# ECE411-Group6.net
KiCad netlist of a schematic drawn in EAGLE
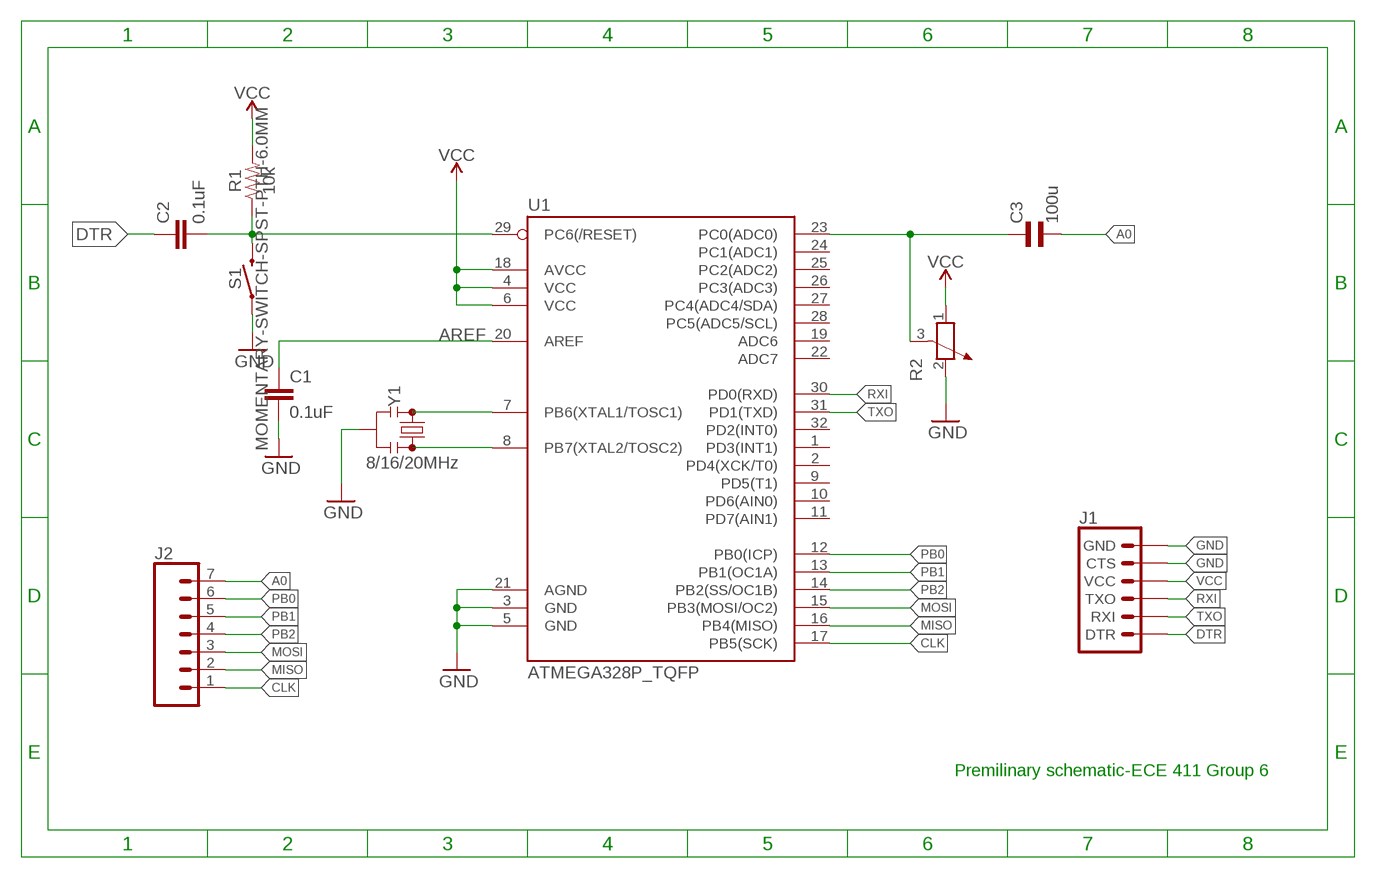
[diagram p0: schematic, sheet 1]

(export (version "E")
  (design (tool "Eeschema 10.0.6"))
  (components
    (comp (ref "C1")
      (value "0.1uF")
      (footprint "eagle-import:0603")
      (libsource (lib "eagle-import") (part "0.1UF-0603-25V-5%"))
    )
    (comp (ref "C2")
      (value "0.1uF")
      (footprint "eagle-import:0603")
      (libsource (lib "eagle-import") (part "0.1UF-0603-25V-5%"))
    )
    (comp (ref "C3")
      (value "100u")
      (footprint "eagle-import:EU25-10")
      (libsource (lib "eagle-import") (part "EL-BI25-10AXIAL"))
    )
    (comp (ref "J1")
      (value "6_PIN_SERIAL_TARGET")
      (footprint "eagle-import:1X06")
      (libsource (lib "eagle-import") (part "6_PIN_SERIAL_TARGET"))
    )
    (comp (ref "J2")
      (value "CONN_07")
      (footprint "eagle-import:1X07")
      (libsource (lib "eagle-import") (part "CONN_07"))
    )
    (comp (ref "R1")
      (value "10k")
      (footprint "eagle-import:0603")
      (libsource (lib "eagle-import") (part "10KOHM-0603-1/10W-1%"))
    )
    (comp (ref "R2")
      (value "POTENTIOMETER_PT-10")
      (footprint "eagle-import:PT-10")
      (libsource (lib "eagle-import") (part "POTENTIOMETER_PT-10"))
    )
    (comp (ref "S1")
      (value "MOMENTARY-SWITCH-SPST-PTH-6.0MM")
      (footprint "eagle-import:TACTILE_SWITCH_PTH_6.0MM")
      (libsource (lib "eagle-import") (part "MOMENTARY-SWITCH-SPST-PTH-6.0MM"))
    )
    (comp (ref "U1")
      (value "ATMEGA328P_TQFP")
      (footprint "eagle-import:TQFP32-08")
      (libsource (lib "eagle-import") (part "ATMEGA328P_TQFP"))
    )
    (comp (ref "Y1")
      (value "8/16/20MHz")
      (footprint "eagle-import:RESONATOR-SMD-3.2X1.3")
      (libsource (lib "eagle-import") (part "RESONATORSMD-3.2X1.3"))
    )
  )
  (nets
    (net (code "1") (name "/AREF") (class "Default")
      (node (ref "C1") (pin "1") (pinfunction "1_1") (pintype "passive"))
      (node (ref "U1") (pin "20") (pinfunction "AREF_20") (pintype "bidirectional"))
    )
    (net (code "2") (name "A0") (class "Default")
      (node (ref "C3") (pin "2") (pinfunction "2_2") (pintype "passive"))
      (node (ref "J2") (pin "7") (pinfunction "7_7") (pintype "passive"))
    )
    (net (code "3") (name "CLK") (class "Default")
      (node (ref "J2") (pin "1") (pinfunction "1_1") (pintype "passive"))
      (node (ref "U1") (pin "17") (pinfunction "PB5(SCK)_17") (pintype "bidirectional"))
    )
    (net (code "4") (name "DTR") (class "Default")
      (node (ref "C2") (pin "1") (pinfunction "1_1") (pintype "passive"))
      (node (ref "J1") (pin "1") (pinfunction "DTR_1") (pintype "passive"))
    )
    (net (code "5") (name "GND") (class "Default")
      (node (ref "C1") (pin "2") (pinfunction "2_2") (pintype "passive"))
      (node (ref "J1") (pin "5") (pinfunction "CTS_5") (pintype "passive"))
      (node (ref "J1") (pin "6") (pinfunction "GND_6") (pintype "passive"))
      (node (ref "R2") (pin "2") (pinfunction "2_2") (pintype "passive"))
      (node (ref "S1") (pin "1") (pinfunction "1_1") (pintype "passive"))
      (node (ref "U1") (pin "21") (pinfunction "AGND_21") (pintype "bidirectional"))
      (node (ref "U1") (pin "3") (pinfunction "GND_3") (pintype "bidirectional"))
      (node (ref "U1") (pin "5") (pinfunction "GND_5") (pintype "bidirectional"))
      (node (ref "Y1") (pin "2") (pinfunction "2_2") (pintype "passive"))
    )
    (net (code "6") (name "MISO") (class "Default")
      (node (ref "J2") (pin "2") (pinfunction "2_2") (pintype "passive"))
      (node (ref "U1") (pin "16") (pinfunction "PB4(MISO)_16") (pintype "bidirectional"))
    )
    (net (code "7") (name "MOSI") (class "Default")
      (node (ref "J2") (pin "3") (pinfunction "3_3") (pintype "passive"))
      (node (ref "U1") (pin "15") (pinfunction "PB3(MOSI/OC2)_15") (pintype "bidirectional"))
    )
    (net (code "8") (name "Net-(S1-2)") (class "Default")
      (node (ref "C2") (pin "2") (pinfunction "2_2") (pintype "passive"))
      (node (ref "R1") (pin "1") (pinfunction "1_1") (pintype "passive"))
      (node (ref "S1") (pin "3") (pinfunction "2_3") (pintype "passive"))
      (node (ref "U1") (pin "29") (pinfunction "PC6(/RESET)_29") (pintype "bidirectional"))
    )
    (net (code "9") (name "Net-(U1-PB6(XTAL1{slash}TOSC1))") (class "Default")
      (node (ref "U1") (pin "7") (pinfunction "PB6(XTAL1/TOSC1)_7") (pintype "bidirectional"))
      (node (ref "Y1") (pin "1") (pinfunction "1_1") (pintype "passive"))
    )
    (net (code "10") (name "Net-(U1-PB7(XTAL2{slash}TOSC2))") (class "Default")
      (node (ref "U1") (pin "8") (pinfunction "PB7(XTAL2/TOSC2)_8") (pintype "bidirectional"))
      (node (ref "Y1") (pin "3") (pinfunction "3_3") (pintype "passive"))
    )
    (net (code "11") (name "Net-(U1-PC0(ADC0))") (class "Default")
      (node (ref "C3") (pin "1") (pinfunction "1_1") (pintype "passive"))
      (node (ref "R2") (pin "3") (pinfunction "3_3") (pintype "passive"))
      (node (ref "U1") (pin "23") (pinfunction "PC0(ADC0)_23") (pintype "bidirectional"))
    )
    (net (code "12") (name "PB0") (class "Default")
      (node (ref "J2") (pin "6") (pinfunction "6_6") (pintype "passive"))
      (node (ref "U1") (pin "12") (pinfunction "PB0(ICP)_12") (pintype "bidirectional"))
    )
    (net (code "13") (name "PB1") (class "Default")
      (node (ref "J2") (pin "5") (pinfunction "5_5") (pintype "passive"))
      (node (ref "U1") (pin "13") (pinfunction "PB1(OC1A)_13") (pintype "bidirectional"))
    )
    (net (code "14") (name "PB2") (class "Default")
      (node (ref "J2") (pin "4") (pinfunction "4_4") (pintype "passive"))
      (node (ref "U1") (pin "14") (pinfunction "PB2(SS/OC1B)_14") (pintype "bidirectional"))
    )
    (net (code "15") (name "RXI") (class "Default")
      (node (ref "J1") (pin "3") (pinfunction "TXO_3") (pintype "passive"))
      (node (ref "U1") (pin "30") (pinfunction "PD0(RXD)_30") (pintype "bidirectional"))
    )
    (net (code "16") (name "TXO") (class "Default")
      (node (ref "J1") (pin "2") (pinfunction "RXI_2") (pintype "passive"))
      (node (ref "U1") (pin "31") (pinfunction "PD1(TXD)_31") (pintype "bidirectional"))
    )
    (net (code "17") (name "VCC") (class "Default")
      (node (ref "J1") (pin "4") (pinfunction "VCC_4") (pintype "passive"))
      (node (ref "R1") (pin "2") (pinfunction "2_2") (pintype "passive"))
      (node (ref "R2") (pin "1") (pinfunction "1_1") (pintype "passive"))
      (node (ref "U1") (pin "18") (pinfunction "AVCC_18") (pintype "bidirectional"))
      (node (ref "U1") (pin "4") (pinfunction "VCC_4") (pintype "bidirectional"))
      (node (ref "U1") (pin "6") (pinfunction "VCC_6") (pintype "bidirectional"))
    )
    (net (code "18") (name "unconnected-(U1-ADC6-Pad19)") (class "Default")
      (node (ref "U1") (pin "19") (pinfunction "ADC6_19") (pintype "bidirectional"))
    )
    (net (code "19") (name "unconnected-(U1-ADC7-Pad22)") (class "Default")
      (node (ref "U1") (pin "22") (pinfunction "ADC7_22") (pintype "bidirectional"))
    )
    (net (code "20") (name "unconnected-(U1-PC1(ADC1)-Pad24)") (class "Default")
      (node (ref "U1") (pin "24") (pinfunction "PC1(ADC1)_24") (pintype "bidirectional"))
    )
    (net (code "21") (name "unconnected-(U1-PC2(ADC2)-Pad25)") (class "Default")
      (node (ref "U1") (pin "25") (pinfunction "PC2(ADC2)_25") (pintype "bidirectional"))
    )
    (net (code "22") (name "unconnected-(U1-PC3(ADC3)-Pad26)") (class "Default")
      (node (ref "U1") (pin "26") (pinfunction "PC3(ADC3)_26") (pintype "bidirectional"))
    )
    (net (code "23") (name "unconnected-(U1-PC4(ADC4{slash}SDA)-Pad27)") (class "Default")
      (node (ref "U1") (pin "27") (pinfunction "PC4(ADC4/SDA)_27") (pintype "bidirectional"))
    )
    (net (code "24") (name "unconnected-(U1-PC5(ADC5{slash}SCL)-Pad28)") (class "Default")
      (node (ref "U1") (pin "28") (pinfunction "PC5(ADC5/SCL)_28") (pintype "bidirectional"))
    )
    (net (code "25") (name "unconnected-(U1-PD2(INT0)-Pad32)") (class "Default")
      (node (ref "U1") (pin "32") (pinfunction "PD2(INT0)_32") (pintype "bidirectional"))
    )
    (net (code "26") (name "unconnected-(U1-PD3(INT1)-Pad1)") (class "Default")
      (node (ref "U1") (pin "1") (pinfunction "PD3(INT1)_1") (pintype "bidirectional"))
    )
    (net (code "27") (name "unconnected-(U1-PD4(XCK{slash}T0)-Pad2)") (class "Default")
      (node (ref "U1") (pin "2") (pinfunction "PD4(XCK/T0)_2") (pintype "bidirectional"))
    )
    (net (code "28") (name "unconnected-(U1-PD5(T1)-Pad9)") (class "Default")
      (node (ref "U1") (pin "9") (pinfunction "PD5(T1)_9") (pintype "bidirectional"))
    )
    (net (code "29") (name "unconnected-(U1-PD6(AIN0)-Pad10)") (class "Default")
      (node (ref "U1") (pin "10") (pinfunction "PD6(AIN0)_10") (pintype "bidirectional"))
    )
    (net (code "30") (name "unconnected-(U1-PD7(AIN1)-Pad11)") (class "Default")
      (node (ref "U1") (pin "11") (pinfunction "PD7(AIN1)_11") (pintype "bidirectional"))
    )
  )
)
